# kelvin_ntc_B.net
KiCad netlist of a schematic drawn in EAGLE
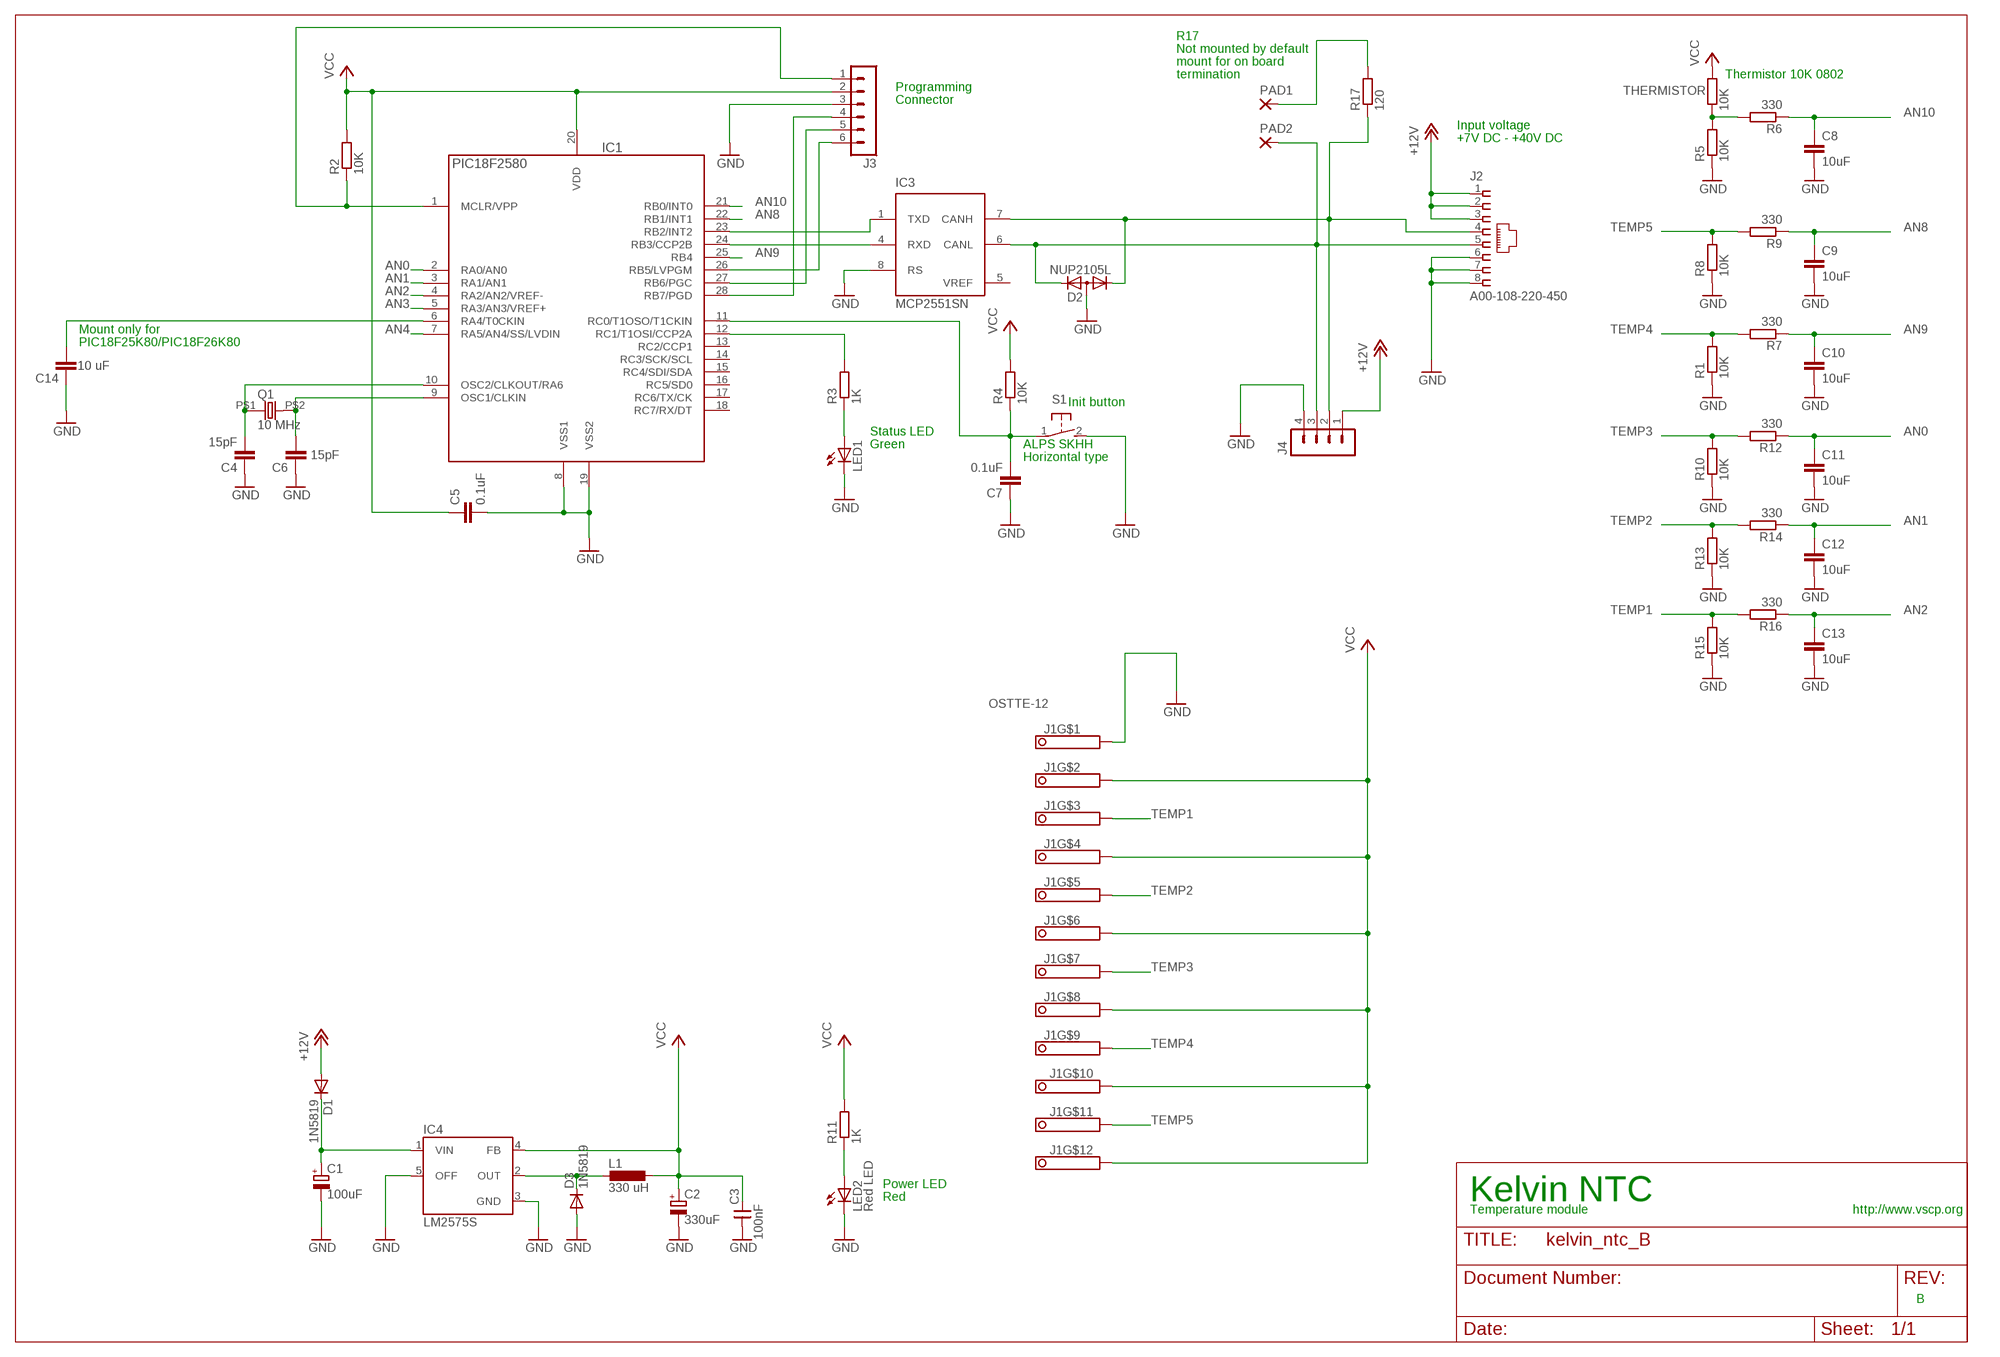
[diagram p0: schematic, sheet 1]

(export (version "E")
  (design (tool "Eeschema 10.0.6"))
  (components
    (comp (ref "C1")
      (value "100uF")
      (footprint "eagle-import:PANASONIC_D")
      (libsource (lib "eagle-import") (part "CPOL-EUD"))
    )
    (comp (ref "C2")
      (value "330uF")
      (footprint "eagle-import:PANASONIC_D")
      (libsource (lib "eagle-import") (part "CPOL-EUD"))
    )
    (comp (ref "C3")
      (value "100nF")
      (footprint "eagle-import:0805")
      (libsource (lib "eagle-import") (part "CNP-0805"))
    )
    (comp (ref "C4")
      (value "15pF")
      (footprint "eagle-import:C0805")
      (libsource (lib "eagle-import") (part "C-EUC0805"))
    )
    (comp (ref "C5")
      (value "0.1uF")
      (footprint "eagle-import:C0805")
      (libsource (lib "eagle-import") (part "C-EUC0805"))
    )
    (comp (ref "C6")
      (value "15pF")
      (footprint "eagle-import:C0805")
      (libsource (lib "eagle-import") (part "C-EUC0805"))
    )
    (comp (ref "C7")
      (value "0.1uF")
      (footprint "eagle-import:C0805")
      (libsource (lib "eagle-import") (part "C-EUC0805"))
    )
    (comp (ref "C8")
      (value "10uF")
      (footprint "eagle-import:C0805")
      (libsource (lib "eagle-import") (part "C-EUC0805"))
    )
    (comp (ref "C9")
      (value "10uF")
      (footprint "eagle-import:C0805")
      (libsource (lib "eagle-import") (part "C-EUC0805"))
    )
    (comp (ref "C10")
      (value "10uF")
      (footprint "eagle-import:C0805")
      (libsource (lib "eagle-import") (part "C-EUC0805"))
    )
    (comp (ref "C11")
      (value "10uF")
      (footprint "eagle-import:C0805")
      (libsource (lib "eagle-import") (part "C-EUC0805"))
    )
    (comp (ref "C12")
      (value "10uF")
      (footprint "eagle-import:C0805")
      (libsource (lib "eagle-import") (part "C-EUC0805"))
    )
    (comp (ref "C13")
      (value "10uF")
      (footprint "eagle-import:C0805")
      (libsource (lib "eagle-import") (part "C-EUC0805"))
    )
    (comp (ref "C14")
      (value "10 uF")
      (footprint "eagle-import:C0805")
      (libsource (lib "eagle-import") (part "C-EUC0805"))
    )
    (comp (ref "D1")
      (value "1N5819")
      (footprint "eagle-import:SOD123")
      (libsource (lib "eagle-import") (part "DIODE-SOD123"))
    )
    (comp (ref "D2")
      (value "NUP2105L")
      (footprint "eagle-import:SOT23")
      (libsource (lib "eagle-import") (part "DIODE-2CA|ACSOT23"))
    )
    (comp (ref "D3")
      (value "1N5819")
      (footprint "eagle-import:SOD123")
      (libsource (lib "eagle-import") (part "DIODE-SOD123"))
    )
    (comp (ref "IC1")
      (value "PIC18F2580")
      (footprint "eagle-import:SO28")
      (libsource (lib "eagle-import") (part "PIC18F252-?I/SOL"))
    )
    (comp (ref "IC3")
      (value "MCP2551SN")
      (footprint "eagle-import:SO-08")
      (libsource (lib "eagle-import") (part "MCP2551SN"))
    )
    (comp (ref "IC4")
      (value "LM2575S")
      (footprint "eagle-import:TO263-5")
      (libsource (lib "eagle-import") (part "LM2575S"))
    )
    (comp (ref "J1")
      (value "OSTTE-12")
      (footprint "eagle-import:PINHEAD-12")
      (libsource (lib "eagle-import") (part "OSTTE-12"))
    )
    (comp (ref "J2")
      (value "A00-108-220-450")
      (footprint "eagle-import:RJ-45")
      (libsource (lib "eagle-import") (part "A00-108-220-450"))
    )
    (comp (ref "J3")
      (value "MA06-1")
      (footprint "eagle-import:MA06-1")
      (libsource (lib "eagle-import") (part "MA06-1"))
    )
    (comp (ref "J4")
      (value "MA04-1")
      (footprint "eagle-import:MA04-1")
      (libsource (lib "eagle-import") (part "MA04-1"))
    )
    (comp (ref "L1")
      (value "330 uH")
      (footprint "eagle-import:DO3316P")
      (libsource (lib "eagle-import") (part "DO3316P"))
    )
    (comp (ref "LED1")
      (value "LEDCHIP-LED0805")
      (footprint "eagle-import:CHIP-LED0805")
      (libsource (lib "eagle-import") (part "LEDCHIP-LED0805"))
    )
    (comp (ref "LED2")
      (value "Red LED")
      (footprint "eagle-import:CHIP-LED0805")
      (libsource (lib "eagle-import") (part "LEDCHIP-LED0805"))
    )
    (comp (ref "PAD1")
      (value "1,6/0,8")
      (footprint "eagle-import:1,6_0,8")
      (libsource (lib "eagle-import") (part "1,6/0,8"))
    )
    (comp (ref "PAD2")
      (value "1,6/0,8")
      (footprint "eagle-import:1,6_0,8")
      (libsource (lib "eagle-import") (part "1,6/0,8"))
    )
    (comp (ref "Q1")
      (value "10 MHz")
      (footprint "eagle-import:9C")
      (libsource (lib "eagle-import") (part "HC-49S"))
    )
    (comp (ref "R1")
      (value "10K")
      (footprint "eagle-import:R0805")
      (libsource (lib "eagle-import") (part "R-EU_R0805"))
    )
    (comp (ref "R2")
      (value "10K")
      (footprint "eagle-import:R0805")
      (libsource (lib "eagle-import") (part "R-EU_R0805"))
    )
    (comp (ref "R3")
      (value "1K")
      (footprint "eagle-import:R0805")
      (libsource (lib "eagle-import") (part "R-EU_R0805"))
    )
    (comp (ref "R4")
      (value "10K")
      (footprint "eagle-import:R0805")
      (libsource (lib "eagle-import") (part "R-EU_R0805"))
    )
    (comp (ref "R5")
      (value "10K")
      (footprint "eagle-import:R0805")
      (libsource (lib "eagle-import") (part "R-EU_R0805"))
    )
    (comp (ref "R6")
      (value "330")
      (footprint "eagle-import:R0805")
      (libsource (lib "eagle-import") (part "R-EU_R0805"))
    )
    (comp (ref "R7")
      (value "330")
      (footprint "eagle-import:R0805")
      (libsource (lib "eagle-import") (part "R-EU_R0805"))
    )
    (comp (ref "R8")
      (value "10K")
      (footprint "eagle-import:R0805")
      (libsource (lib "eagle-import") (part "R-EU_R0805"))
    )
    (comp (ref "R9")
      (value "330")
      (footprint "eagle-import:R0805")
      (libsource (lib "eagle-import") (part "R-EU_R0805"))
    )
    (comp (ref "R10")
      (value "10K")
      (footprint "eagle-import:R0805")
      (libsource (lib "eagle-import") (part "R-EU_R0805"))
    )
    (comp (ref "R11")
      (value "1K")
      (footprint "eagle-import:R0805")
      (libsource (lib "eagle-import") (part "R-EU_R0805"))
    )
    (comp (ref "R12")
      (value "330")
      (footprint "eagle-import:R0805")
      (libsource (lib "eagle-import") (part "R-EU_R0805"))
    )
    (comp (ref "R13")
      (value "10K")
      (footprint "eagle-import:R0805")
      (libsource (lib "eagle-import") (part "R-EU_R0805"))
    )
    (comp (ref "R14")
      (value "330")
      (footprint "eagle-import:R0805")
      (libsource (lib "eagle-import") (part "R-EU_R0805"))
    )
    (comp (ref "R15")
      (value "10K")
      (footprint "eagle-import:R0805")
      (libsource (lib "eagle-import") (part "R-EU_R0805"))
    )
    (comp (ref "R16")
      (value "330")
      (footprint "eagle-import:R0805")
      (libsource (lib "eagle-import") (part "R-EU_R0805"))
    )
    (comp (ref "R17")
      (value "120")
      (footprint "eagle-import:R0805")
      (libsource (lib "eagle-import") (part "R-EU_R0805"))
    )
    (comp (ref "S1")
      (value "31-XX")
      (footprint "eagle-import:B3F-31XX")
      (fields (field (name "MPN") "B3F-3100"))
      (libsource (lib "eagle-import") (part "31-XX"))
    )
    (comp (ref "THERMISTOR")
      (value "10K")
      (footprint "eagle-import:R0805")
      (libsource (lib "eagle-import") (part "R-EU_R0805"))
    )
  )
  (nets
    (net (code "1") (name "+12V") (class "Default")
      (node (ref "D1") (pin "A") (pinfunction "A_A") (pintype "passive"))
      (node (ref "J2") (pin "1") (pinfunction "1_1") (pintype "passive"))
      (node (ref "J2") (pin "2") (pinfunction "2_2") (pintype "passive"))
      (node (ref "J2") (pin "3") (pinfunction "3_3") (pintype "passive"))
      (node (ref "J4") (pin "1") (pinfunction "1_1") (pintype "passive"))
    )
    (net (code "2") (name "/AN0") (class "Default")
      (node (ref "C11") (pin "1") (pinfunction "1_1") (pintype "passive"))
      (node (ref "IC1") (pin "2") (pinfunction "RA0/AN0_2") (pintype "bidirectional"))
      (node (ref "R12") (pin "1") (pinfunction "1_1") (pintype "passive"))
    )
    (net (code "3") (name "/AN1") (class "Default")
      (node (ref "C12") (pin "1") (pinfunction "1_1") (pintype "passive"))
      (node (ref "IC1") (pin "3") (pinfunction "RA1/AN1_3") (pintype "bidirectional"))
      (node (ref "R14") (pin "1") (pinfunction "1_1") (pintype "passive"))
    )
    (net (code "4") (name "/AN2") (class "Default")
      (node (ref "C13") (pin "1") (pinfunction "1_1") (pintype "passive"))
      (node (ref "IC1") (pin "4") (pinfunction "RA2/AN2/VREF-_4") (pintype "bidirectional"))
      (node (ref "R16") (pin "1") (pinfunction "1_1") (pintype "passive"))
    )
    (net (code "5") (name "/AN3") (class "Default")
      (node (ref "IC1") (pin "5") (pinfunction "RA3/AN3/VREF+_5") (pintype "bidirectional"))
    )
    (net (code "6") (name "/AN4") (class "Default")
      (node (ref "IC1") (pin "7") (pinfunction "RA5/AN4/SS/LVDIN_7") (pintype "bidirectional"))
    )
    (net (code "7") (name "/AN8") (class "Default")
      (node (ref "C9") (pin "1") (pinfunction "1_1") (pintype "passive"))
      (node (ref "IC1") (pin "22") (pinfunction "RB1/INT1_22") (pintype "bidirectional"))
      (node (ref "R9") (pin "1") (pinfunction "1_1") (pintype "passive"))
    )
    (net (code "8") (name "/AN9") (class "Default")
      (node (ref "C10") (pin "1") (pinfunction "1_1") (pintype "passive"))
      (node (ref "IC1") (pin "25") (pinfunction "RB4_25") (pintype "bidirectional"))
      (node (ref "R7") (pin "1") (pinfunction "1_1") (pintype "passive"))
    )
    (net (code "9") (name "/AN10") (class "Default")
      (node (ref "C8") (pin "1") (pinfunction "1_1") (pintype "passive"))
      (node (ref "IC1") (pin "21") (pinfunction "RB0/INT0_21") (pintype "bidirectional"))
      (node (ref "R6") (pin "1") (pinfunction "1_1") (pintype "passive"))
    )
    (net (code "10") (name "/TEMP1") (class "Default")
      (node (ref "J1") (pin "3") (pinfunction "K_3") (pintype "passive"))
      (node (ref "R15") (pin "2") (pinfunction "2_2") (pintype "passive"))
      (node (ref "R16") (pin "2") (pinfunction "2_2") (pintype "passive"))
    )
    (net (code "11") (name "/TEMP2") (class "Default")
      (node (ref "J1") (pin "5") (pinfunction "K_5") (pintype "passive"))
      (node (ref "R13") (pin "2") (pinfunction "2_2") (pintype "passive"))
      (node (ref "R14") (pin "2") (pinfunction "2_2") (pintype "passive"))
    )
    (net (code "12") (name "/TEMP3") (class "Default")
      (node (ref "J1") (pin "7") (pinfunction "K_7") (pintype "passive"))
      (node (ref "R10") (pin "2") (pinfunction "2_2") (pintype "passive"))
      (node (ref "R12") (pin "2") (pinfunction "2_2") (pintype "passive"))
    )
    (net (code "13") (name "/TEMP4") (class "Default")
      (node (ref "J1") (pin "9") (pinfunction "K_9") (pintype "passive"))
      (node (ref "R1") (pin "2") (pinfunction "2_2") (pintype "passive"))
      (node (ref "R7") (pin "2") (pinfunction "2_2") (pintype "passive"))
    )
    (net (code "14") (name "/TEMP5") (class "Default")
      (node (ref "J1") (pin "11") (pinfunction "K_11") (pintype "passive"))
      (node (ref "R8") (pin "2") (pinfunction "2_2") (pintype "passive"))
      (node (ref "R9") (pin "2") (pinfunction "2_2") (pintype "passive"))
    )
    (net (code "15") (name "/VREF") (class "Default")
      (node (ref "IC3") (pin "5") (pinfunction "VREF_5") (pintype "power_in"))
    )
    (net (code "16") (name "GND") (class "Default")
      (node (ref "C1") (pin "-") (pinfunction "-_-") (pintype "passive"))
      (node (ref "C10") (pin "2") (pinfunction "2_2") (pintype "passive"))
      (node (ref "C11") (pin "2") (pinfunction "2_2") (pintype "passive"))
      (node (ref "C12") (pin "2") (pinfunction "2_2") (pintype "passive"))
      (node (ref "C13") (pin "2") (pinfunction "2_2") (pintype "passive"))
      (node (ref "C14") (pin "1") (pinfunction "1_1") (pintype "passive"))
      (node (ref "C2") (pin "-") (pinfunction "-_-") (pintype "passive"))
      (node (ref "C3") (pin "1") (pinfunction "1_1") (pintype "passive"))
      (node (ref "C4") (pin "1") (pinfunction "1_1") (pintype "passive"))
      (node (ref "C5") (pin "2") (pinfunction "2_2") (pintype "passive"))
      (node (ref "C6") (pin "1") (pinfunction "1_1") (pintype "passive"))
      (node (ref "C7") (pin "1") (pinfunction "1_1") (pintype "passive"))
      (node (ref "C8") (pin "2") (pinfunction "2_2") (pintype "passive"))
      (node (ref "C9") (pin "2") (pinfunction "2_2") (pintype "passive"))
      (node (ref "D2") (pin "3") (pinfunction "A_3") (pintype "passive"))
      (node (ref "D3") (pin "A") (pinfunction "A_A") (pintype "passive"))
      (node (ref "IC1") (pin "19") (pinfunction "VSS2_19") (pintype "power_in"))
      (node (ref "IC1") (pin "8") (pinfunction "VSS1_8") (pintype "power_in"))
      (node (ref "IC3") (pin "8") (pinfunction "RS_8") (pintype "input"))
      (node (ref "IC4") (pin "3") (pinfunction "GND_3") (pintype "power_in"))
      (node (ref "IC4") (pin "5") (pinfunction "OFF_5") (pintype "input"))
      (node (ref "J1") (pin "1") (pinfunction "K_1") (pintype "passive"))
      (node (ref "J2") (pin "6") (pinfunction "6_6") (pintype "passive"))
      (node (ref "J2") (pin "7") (pinfunction "7_7") (pintype "passive"))
      (node (ref "J2") (pin "8") (pinfunction "8_8") (pintype "passive"))
      (node (ref "J3") (pin "3") (pinfunction "3_3") (pintype "passive"))
      (node (ref "J4") (pin "4") (pinfunction "4_4") (pintype "passive"))
      (node (ref "LED1") (pin "C") (pinfunction "C_C") (pintype "passive"))
      (node (ref "LED2") (pin "C") (pinfunction "C_C") (pintype "passive"))
      (node (ref "R1") (pin "1") (pinfunction "1_1") (pintype "passive"))
      (node (ref "R10") (pin "1") (pinfunction "1_1") (pintype "passive"))
      (node (ref "R13") (pin "1") (pinfunction "1_1") (pintype "passive"))
      (node (ref "R15") (pin "1") (pinfunction "1_1") (pintype "passive"))
      (node (ref "R5") (pin "1") (pinfunction "1_1") (pintype "passive"))
      (node (ref "R8") (pin "1") (pinfunction "1_1") (pintype "passive"))
      (node (ref "S1") (pin "2") (pinfunction "S_2") (pintype "passive"))
    )
    (net (code "17") (name "Net-(D2-K1)") (class "Default")
      (node (ref "D2") (pin "1") (pinfunction "K1_1") (pintype "passive"))
      (node (ref "IC3") (pin "7") (pinfunction "CANH_7") (pintype "bidirectional"))
      (node (ref "J2") (pin "4") (pinfunction "4_4") (pintype "passive"))
      (node (ref "J4") (pin "2") (pinfunction "2_2") (pintype "passive"))
      (node (ref "R17") (pin "1") (pinfunction "1_1") (pintype "passive"))
    )
    (net (code "18") (name "Net-(D2-K2)") (class "Default")
      (node (ref "D2") (pin "2") (pinfunction "K2_2") (pintype "passive"))
      (node (ref "IC3") (pin "6") (pinfunction "CANL_6") (pintype "bidirectional"))
      (node (ref "J2") (pin "5") (pinfunction "5_5") (pintype "passive"))
      (node (ref "J4") (pin "3") (pinfunction "3_3") (pintype "passive"))
      (node (ref "PAD2") (pin "1") (pinfunction "P_1") (pintype "passive"))
    )
    (net (code "19") (name "Net-(IC1-MCLR{slash}VPP)") (class "Default")
      (node (ref "IC1") (pin "1") (pinfunction "MCLR/VPP_1") (pintype "input"))
      (node (ref "J3") (pin "1") (pinfunction "1_1") (pintype "passive"))
      (node (ref "R2") (pin "1") (pinfunction "1_1") (pintype "passive"))
    )
    (net (code "20") (name "Net-(IC1-OSC1{slash}CLKIN)") (class "Default")
      (node (ref "C6") (pin "2") (pinfunction "2_2") (pintype "passive"))
      (node (ref "IC1") (pin "9") (pinfunction "OSC1/CLKIN_9") (pintype "input"))
      (node (ref "Q1") (pin "P$2") (pinfunction "2_P$2") (pintype "passive"))
    )
    (net (code "21") (name "Net-(IC1-OSC2{slash}CLKOUT{slash}RA6)") (class "Default")
      (node (ref "C4") (pin "2") (pinfunction "2_2") (pintype "passive"))
      (node (ref "IC1") (pin "10") (pinfunction "OSC2/CLKOUT/RA6_10") (pintype "output"))
      (node (ref "Q1") (pin "P$1") (pinfunction "1_P$1") (pintype "passive"))
    )
    (net (code "22") (name "Net-(IC1-RA4{slash}T0CKIN)") (class "Default")
      (node (ref "C14") (pin "2") (pinfunction "2_2") (pintype "passive"))
      (node (ref "IC1") (pin "6") (pinfunction "RA4/T0CKIN_6") (pintype "open_collector"))
    )
    (net (code "23") (name "Net-(IC1-RB2{slash}INT2)") (class "Default")
      (node (ref "IC1") (pin "23") (pinfunction "RB2/INT2_23") (pintype "bidirectional"))
      (node (ref "IC3") (pin "1") (pinfunction "TXD_1") (pintype "input"))
    )
    (net (code "24") (name "Net-(IC1-RB3{slash}CCP2B)") (class "Default")
      (node (ref "IC1") (pin "24") (pinfunction "RB3/CCP2B_24") (pintype "bidirectional"))
      (node (ref "IC3") (pin "4") (pinfunction "RXD_4") (pintype "output"))
    )
    (net (code "25") (name "Net-(IC1-RB5{slash}LVPGM)") (class "Default")
      (node (ref "IC1") (pin "26") (pinfunction "RB5/LVPGM_26") (pintype "bidirectional"))
      (node (ref "J3") (pin "6") (pinfunction "6_6") (pintype "passive"))
    )
    (net (code "26") (name "Net-(IC1-RB6{slash}PGC)") (class "Default")
      (node (ref "IC1") (pin "27") (pinfunction "RB6/PGC_27") (pintype "bidirectional"))
      (node (ref "J3") (pin "5") (pinfunction "5_5") (pintype "passive"))
    )
    (net (code "27") (name "Net-(IC1-RB7{slash}PGD)") (class "Default")
      (node (ref "IC1") (pin "28") (pinfunction "RB7/PGD_28") (pintype "bidirectional"))
      (node (ref "J3") (pin "4") (pinfunction "4_4") (pintype "passive"))
    )
    (net (code "28") (name "Net-(IC1-RC0{slash}T1OSO{slash}T1CKIN)") (class "Default")
      (node (ref "C7") (pin "2") (pinfunction "2_2") (pintype "passive"))
      (node (ref "IC1") (pin "11") (pinfunction "RC0/T1OSO/T1CKIN_11") (pintype "bidirectional"))
      (node (ref "R4") (pin "1") (pinfunction "1_1") (pintype "passive"))
      (node (ref "S1") (pin "1") (pinfunction "P_1") (pintype "passive"))
    )
    (net (code "29") (name "Net-(IC1-RC1{slash}T1OSI{slash}CCP2A)") (class "Default")
      (node (ref "IC1") (pin "12") (pinfunction "RC1/T1OSI/CCP2A_12") (pintype "bidirectional"))
      (node (ref "R3") (pin "2") (pinfunction "2_2") (pintype "passive"))
    )
    (net (code "30") (name "Net-(IC4-OUT)") (class "Default")
      (node (ref "D3") (pin "C") (pinfunction "C_C") (pintype "passive"))
      (node (ref "IC4") (pin "2") (pinfunction "OUT_2") (pintype "output"))
      (node (ref "L1") (pin "1") (pinfunction "1_1") (pintype "passive"))
    )
    (net (code "31") (name "Net-(IC4-VIN)") (class "Default")
      (node (ref "C1") (pin "+") (pinfunction "+_+") (pintype "passive"))
      (node (ref "D1") (pin "C") (pinfunction "C_C") (pintype "passive"))
      (node (ref "IC4") (pin "1") (pinfunction "VIN_1") (pintype "power_in"))
    )
    (net (code "32") (name "Net-(LED1-PadA)") (class "Default")
      (node (ref "LED1") (pin "A") (pinfunction "A_A") (pintype "passive"))
      (node (ref "R3") (pin "1") (pinfunction "1_1") (pintype "passive"))
    )
    (net (code "33") (name "Net-(LED2-PadA)") (class "Default")
      (node (ref "LED2") (pin "A") (pinfunction "A_A") (pintype "passive"))
      (node (ref "R11") (pin "1") (pinfunction "1_1") (pintype "passive"))
    )
    (net (code "34") (name "Net-(PAD1-P)") (class "Default")
      (node (ref "PAD1") (pin "1") (pinfunction "P_1") (pintype "passive"))
      (node (ref "R17") (pin "2") (pinfunction "2_2") (pintype "passive"))
    )
    (net (code "35") (name "Net-(R5-Pad2)") (class "Default")
      (node (ref "R5") (pin "2") (pinfunction "2_2") (pintype "passive"))
      (node (ref "R6") (pin "2") (pinfunction "2_2") (pintype "passive"))
      (node (ref "THERMISTOR") (pin "1") (pinfunction "1_1") (pintype "passive"))
    )
    (net (code "36") (name "VCC") (class "Default")
      (node (ref "C2") (pin "+") (pinfunction "+_+") (pintype "passive"))
      (node (ref "C3") (pin "2") (pinfunction "2_2") (pintype "passive"))
      (node (ref "C5") (pin "1") (pinfunction "1_1") (pintype "passive"))
      (node (ref "IC1") (pin "20") (pinfunction "VDD_20") (pintype "power_in"))
      (node (ref "IC4") (pin "4") (pinfunction "FB_4") (pintype "input"))
      (node (ref "J1") (pin "10") (pinfunction "K_10") (pintype "passive"))
      (node (ref "J1") (pin "12") (pinfunction "K_12") (pintype "passive"))
      (node (ref "J1") (pin "2") (pinfunction "K_2") (pintype "passive"))
      (node (ref "J1") (pin "4") (pinfunction "K_4") (pintype "passive"))
      (node (ref "J1") (pin "6") (pinfunction "K_6") (pintype "passive"))
      (node (ref "J1") (pin "8") (pinfunction "K_8") (pintype "passive"))
      (node (ref "J3") (pin "2") (pinfunction "2_2") (pintype "passive"))
      (node (ref "L1") (pin "2") (pinfunction "2_2") (pintype "passive"))
      (node (ref "R11") (pin "2") (pinfunction "2_2") (pintype "passive"))
      (node (ref "R2") (pin "2") (pinfunction "2_2") (pintype "passive"))
      (node (ref "R4") (pin "2") (pinfunction "2_2") (pintype "passive"))
      (node (ref "THERMISTOR") (pin "2") (pinfunction "2_2") (pintype "passive"))
    )
    (net (code "37") (name "unconnected-(IC1-RC2{slash}CCP1-Pad13)") (class "Default")
      (node (ref "IC1") (pin "13") (pinfunction "RC2/CCP1_13") (pintype "bidirectional"))
    )
    (net (code "38") (name "unconnected-(IC1-RC3{slash}SCK{slash}SCL-Pad14)") (class "Default")
      (node (ref "IC1") (pin "14") (pinfunction "RC3/SCK/SCL_14") (pintype "bidirectional"))
    )
    (net (code "39") (name "unconnected-(IC1-RC4{slash}SDI{slash}SDA-Pad15)") (class "Default")
      (node (ref "IC1") (pin "15") (pinfunction "RC4/SDI/SDA_15") (pintype "bidirectional"))
    )
    (net (code "40") (name "unconnected-(IC1-RC5{slash}SD0-Pad16)") (class "Default")
      (node (ref "IC1") (pin "16") (pinfunction "RC5/SD0_16") (pintype "bidirectional"))
    )
    (net (code "41") (name "unconnected-(IC1-RC6{slash}TX{slash}CK-Pad17)") (class "Default")
      (node (ref "IC1") (pin "17") (pinfunction "RC6/TX/CK_17") (pintype "bidirectional"))
    )
    (net (code "42") (name "unconnected-(IC1-RC7{slash}RX{slash}DT-Pad18)") (class "Default")
      (node (ref "IC1") (pin "18") (pinfunction "RC7/RX/DT_18") (pintype "bidirectional"))
    )
  )
)
